# Receiver_V2.net
KiCad netlist of a schematic drawn in Altium Designer
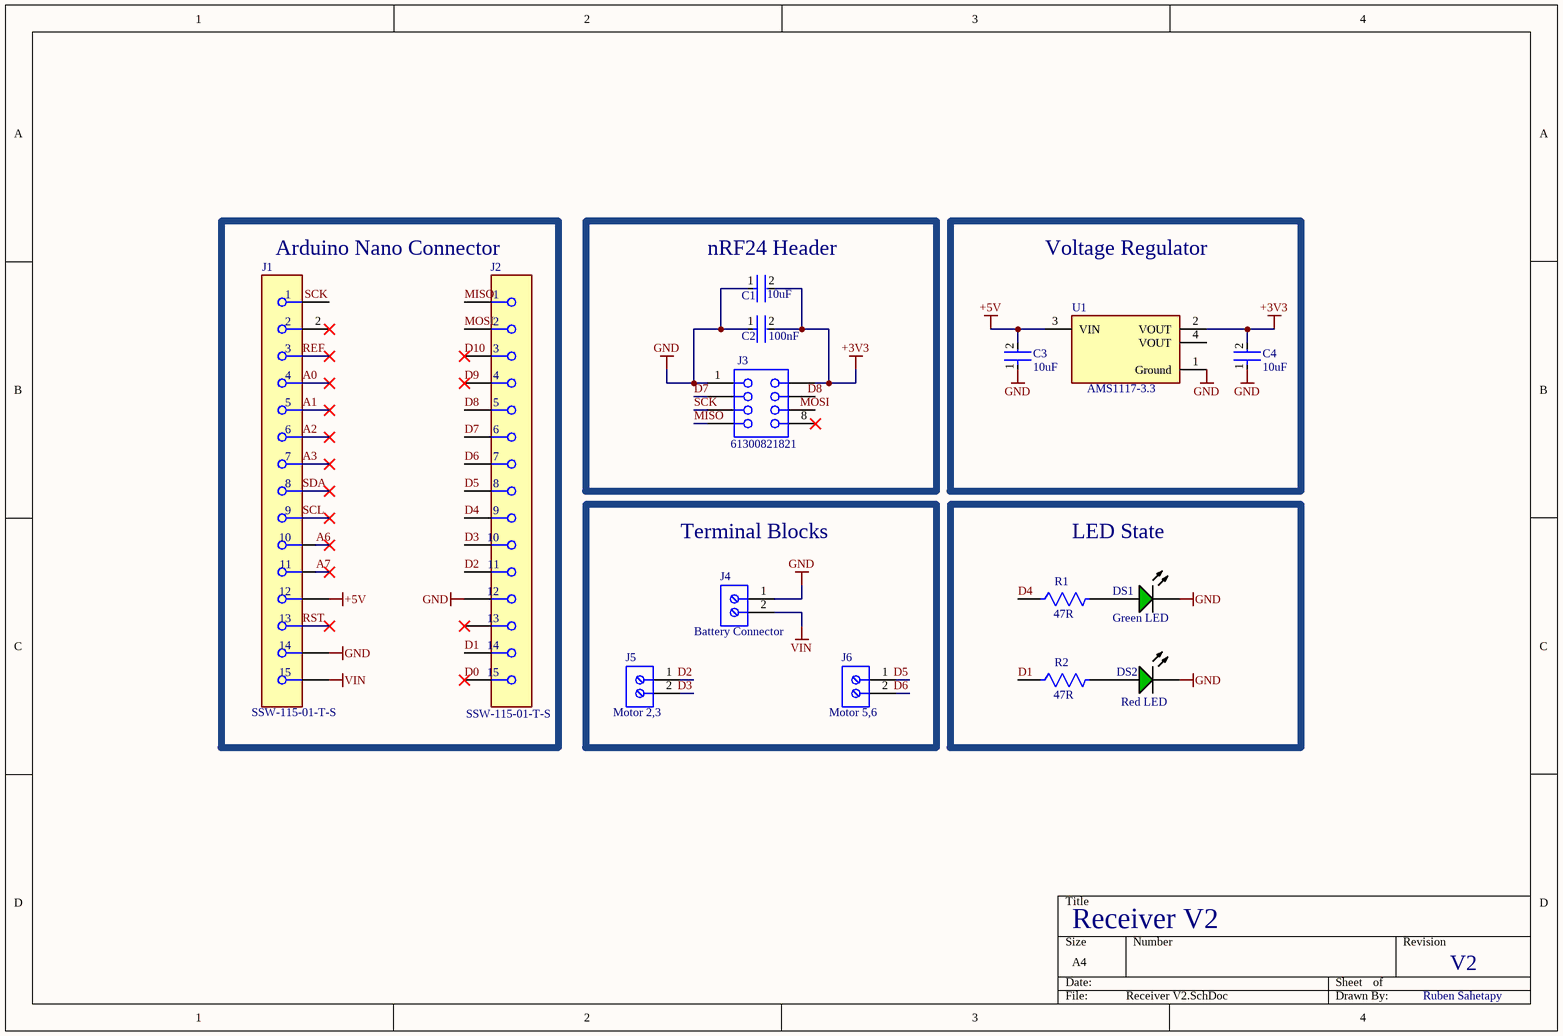
[diagram p0: Receiver V2.SchDoc]

(export (version "E")
  (design (tool "Eeschema 10.0.6"))
  (components
    (comp (ref "C1")
      (value "10uF")
      (footprint "FP-C0805C-DG-MFG")
      (description "CAP CER 10UF 10V X5R 0805")
      (fields (field (name "TOLERANCE") "10%") (field (name "MANUFACTURER PART NUMBER") "C0805C106K8PACTU"))
      (libsource (lib "Altium Content Vault") (part "11868f565c42a9108669ba33697ecf6"))
    )
    (comp (ref "C2")
      (value "100nF")
      (footprint "FP-CC0805-0_85-MFG")
      (description "CAP CER 0.1UF 16V X7R 0805")
      (fields
        (field (name "MANUFACTURER PART NUMBER") "CC0805KRX7R7BB104")
        (field (name "MANUFACTURER") "Yageo")
      )
      (libsource (lib "Altium Content Vault") (part "11868f565c42a9108669ba33697ecf6"))
    )
    (comp (ref "C3")
      (value "10uF")
      (footprint "FP-C0805C-DG-MFG")
      (description "CAP CER 10UF 10V X5R 0805")
      (fields (field (name "TOLERANCE") "10%") (field (name "MANUFACTURER PART NUMBER") "C0805C106K8PACTU"))
      (libsource (lib "Altium Content Vault") (part "11868f565c42a9108669ba33697ecf6"))
    )
    (comp (ref "C4")
      (value "10uF")
      (footprint "FP-C0805C-DG-MFG")
      (description "CAP CER 10UF 10V X5R 0805")
      (fields (field (name "TOLERANCE") "10%") (field (name "MANUFACTURER PART NUMBER") "C0805C106K8PACTU"))
      (libsource (lib "Altium Content Vault") (part "11868f565c42a9108669ba33697ecf6"))
    )
    (comp (ref "DS1")
      (value "Green LED")
      (footprint "AVAG-HSMX-C170_V")
      (description "Chip LED, Green, 2.2 V, -40 to 85 degC, 2-Pin SMD, Pb-Free, Tape and Reel")
      (fields (field (name "MANUFACTURER") "Avago"))
      (libsource (lib "Altium Content Vault") (part "LED_GREEN_A1K2-2"))
    )
    (comp (ref "DS2")
      (value "Red LED")
      (footprint "AVAG-HSMX-C170_V")
      (description "Chip LED, Green, 2.2 V, -40 to 85 degC, 2-Pin SMD, Pb-Free, Tape and Reel")
      (fields (field (name "MANUFACTURER") "Avago"))
      (libsource (lib "Altium Content Vault") (part "LED_GREEN_A1K2-2"))
    )
    (comp (ref "J1")
      (value "SSW-115-01-T-S")
      (footprint "FP-SSW-115-01-T-S-MFG")
      (description "CONN RCPT 15POS 0.1 TIN PCB")
      (libsource (lib "") (part "de2cdd76613f87adcba81301aaab7e9_1"))
    )
    (comp (ref "J2")
      (value "SSW-115-01-T-S")
      (footprint "FP-SSW-115-01-T-S-MFG")
      (description "CONN RCPT 15POS 0.1 TIN PCB")
      (libsource (lib "Altium Content Vault") (part "de2cdd76613f87adcba81301aaab7e9"))
    )
    (comp (ref "J3")
      (value "61300821821")
      (footprint "61300821821")
      (libsource (lib "Altium Content Vault") (part "Header_Female_2R_08P"))
    )
    (comp (ref "J4")
      (value "Battery Connector")
      (footprint "691214110002")
      (fields (field (name "VOLTAGE") "300V"))
      (libsource (lib "Altium Content Vault") (part "TBL - 1R - 02P - Screw"))
    )
    (comp (ref "J5")
      (value "Motor 2,3")
      (footprint "691214110002")
      (fields (field (name "VOLTAGE") "300V"))
      (libsource (lib "Altium Content Vault") (part "TBL - 1R - 02P - Screw"))
    )
    (comp (ref "J6")
      (value "Motor 5,6")
      (footprint "691214110002")
      (fields (field (name "VOLTAGE") "300V"))
      (libsource (lib "Altium Content Vault") (part "TBL - 1R - 02P - Screw"))
    )
    (comp (ref "R1")
      (value "47R")
      (footprint "FP-RC1206-MFG")
      (description "RES SMD 0 OHM JUMPER 1/4W 1206")
      (fields
        (field (name "MANUFACTURER PART NUMBER") "RC1206JR-070RL")
        (field (name "MANUFACTURER") "YAGEO")
      )
      (libsource (lib "Altium Content Vault") (part "1029c3af85768c4190bb7ad29bc67b5"))
    )
    (comp (ref "R2")
      (value "47R")
      (footprint "FP-RC1206-MFG")
      (description "RES SMD 0 OHM JUMPER 1/4W 1206")
      (fields
        (field (name "MANUFACTURER PART NUMBER") "RC1206JR-070RL")
        (field (name "MANUFACTURER") "YAGEO")
      )
      (libsource (lib "Altium Content Vault") (part "1029c3af85768c4190bb7ad29bc67b5"))
    )
    (comp (ref "U1")
      (value "AMS1117-3.3")
      (footprint "FP-AMS1117-IPC_C")
      (description "LDO Voltage Regulators 1A, 3.3V")
      (fields
        (field (name "OCTOPART") "https://octopart.com/ams1117-3.3-advanced+monolithic+systems-25899300")
        (field (name "MANUFACTURER") "Advanced Monolithic Systems")
      )
      (libsource (lib "Altium Content Vault") (part "8bdbb5f8e77002000e30dd2845d0354"))
    )
  )
  (nets
    (net (code "1") (name "+3V3") (class "Default")
      (node (ref "C1") (pin "2") (pinfunction "2_2") (pintype "passive"))
      (node (ref "C2") (pin "2") (pinfunction "2_2") (pintype "passive"))
      (node (ref "C4") (pin "2") (pinfunction "2_2") (pintype "passive"))
      (node (ref "J3") (pin "2") (pinfunction "2_2") (pintype "passive"))
      (node (ref "U1") (pin "2") (pinfunction "VOUT_2") (pintype "passive"))
    )
    (net (code "2") (name "+5V") (class "Default")
      (node (ref "C3") (pin "2") (pinfunction "2_2") (pintype "passive"))
      (node (ref "J1") (pin "12") (pinfunction "12_12") (pintype "passive"))
      (node (ref "U1") (pin "3") (pinfunction "VIN_3") (pintype "power_in"))
    )
    (net (code "3") (name "/A0") (class "Default")
      (node (ref "J1") (pin "4") (pinfunction "4_4") (pintype "passive+no_connect"))
    )
    (net (code "4") (name "/A1") (class "Default")
      (node (ref "J1") (pin "5") (pinfunction "5_5") (pintype "passive+no_connect"))
    )
    (net (code "5") (name "/A2") (class "Default")
      (node (ref "J1") (pin "6") (pinfunction "6_6") (pintype "passive+no_connect"))
    )
    (net (code "6") (name "/A3") (class "Default")
      (node (ref "J1") (pin "7") (pinfunction "7_7") (pintype "passive+no_connect"))
    )
    (net (code "7") (name "/A6") (class "Default")
      (node (ref "J1") (pin "10") (pinfunction "10_10") (pintype "passive+no_connect"))
    )
    (net (code "8") (name "/A7") (class "Default")
      (node (ref "J1") (pin "11") (pinfunction "11_11") (pintype "passive+no_connect"))
    )
    (net (code "9") (name "/D0") (class "Default")
      (node (ref "J2") (pin "15") (pinfunction "15_15") (pintype "passive+no_connect"))
    )
    (net (code "10") (name "/D1") (class "Default")
      (node (ref "J2") (pin "14") (pinfunction "14_14") (pintype "passive"))
      (node (ref "R2") (pin "1") (pinfunction "1_1") (pintype "passive"))
    )
    (net (code "11") (name "/D2") (class "Default")
      (node (ref "J2") (pin "11") (pinfunction "11_11") (pintype "passive"))
      (node (ref "J5") (pin "1") (pinfunction "1_1") (pintype "passive"))
    )
    (net (code "12") (name "/D3") (class "Default")
      (node (ref "J2") (pin "10") (pinfunction "10_10") (pintype "passive"))
      (node (ref "J5") (pin "2") (pinfunction "2_2") (pintype "passive"))
    )
    (net (code "13") (name "/D4") (class "Default")
      (node (ref "J2") (pin "9") (pinfunction "9_9") (pintype "passive"))
      (node (ref "R1") (pin "1") (pinfunction "1_1") (pintype "passive"))
    )
    (net (code "14") (name "/D5") (class "Default")
      (node (ref "J2") (pin "8") (pinfunction "8_8") (pintype "passive"))
      (node (ref "J6") (pin "1") (pinfunction "1_1") (pintype "passive"))
    )
    (net (code "15") (name "/D6") (class "Default")
      (node (ref "J2") (pin "7") (pinfunction "7_7") (pintype "passive"))
      (node (ref "J6") (pin "2") (pinfunction "2_2") (pintype "passive"))
    )
    (net (code "16") (name "/D7") (class "Default")
      (node (ref "J2") (pin "6") (pinfunction "6_6") (pintype "passive"))
      (node (ref "J3") (pin "3") (pinfunction "3_3") (pintype "passive"))
    )
    (net (code "17") (name "/D8") (class "Default")
      (node (ref "J2") (pin "5") (pinfunction "5_5") (pintype "passive"))
      (node (ref "J3") (pin "4") (pinfunction "4_4") (pintype "passive"))
    )
    (net (code "18") (name "/D9") (class "Default")
      (node (ref "J2") (pin "4") (pinfunction "4_4") (pintype "passive+no_connect"))
    )
    (net (code "19") (name "/D10") (class "Default")
      (node (ref "J2") (pin "3") (pinfunction "3_3") (pintype "passive+no_connect"))
    )
    (net (code "20") (name "/MISO") (class "Default")
      (node (ref "J2") (pin "1") (pinfunction "1_1") (pintype "passive"))
      (node (ref "J3") (pin "7") (pinfunction "7_7") (pintype "passive"))
    )
    (net (code "21") (name "/MOSI") (class "Default")
      (node (ref "J2") (pin "2") (pinfunction "2_2") (pintype "passive"))
      (node (ref "J3") (pin "6") (pinfunction "6_6") (pintype "passive"))
    )
    (net (code "22") (name "/REF") (class "Default")
      (node (ref "J1") (pin "3") (pinfunction "3_3") (pintype "passive+no_connect"))
    )
    (net (code "23") (name "/RST") (class "Default")
      (node (ref "J1") (pin "13") (pinfunction "13_13") (pintype "passive+no_connect"))
    )
    (net (code "24") (name "/SCK") (class "Default")
      (node (ref "J1") (pin "1") (pinfunction "1_1") (pintype "passive"))
      (node (ref "J3") (pin "5") (pinfunction "5_5") (pintype "passive"))
    )
    (net (code "25") (name "/SCL") (class "Default")
      (node (ref "J1") (pin "9") (pinfunction "9_9") (pintype "passive+no_connect"))
    )
    (net (code "26") (name "/SDA") (class "Default")
      (node (ref "J1") (pin "8") (pinfunction "8_8") (pintype "passive+no_connect"))
    )
    (net (code "27") (name "GND") (class "Default")
      (node (ref "C1") (pin "1") (pinfunction "1_1") (pintype "passive"))
      (node (ref "C2") (pin "1") (pinfunction "1_1") (pintype "passive"))
      (node (ref "C3") (pin "1") (pinfunction "1_1") (pintype "passive"))
      (node (ref "C4") (pin "1") (pinfunction "1_1") (pintype "passive"))
      (node (ref "DS1") (pin "2") (pinfunction "K_2") (pintype "passive"))
      (node (ref "DS2") (pin "2") (pinfunction "K_2") (pintype "passive"))
      (node (ref "J1") (pin "14") (pinfunction "14_14") (pintype "passive"))
      (node (ref "J2") (pin "12") (pinfunction "12_12") (pintype "passive"))
      (node (ref "J3") (pin "1") (pinfunction "1_1") (pintype "passive"))
      (node (ref "J4") (pin "1") (pinfunction "1_1") (pintype "passive"))
      (node (ref "U1") (pin "1") (pinfunction "Ground_1") (pintype "power_in"))
    )
    (net (code "28") (name "Net-(DS1-A)") (class "Default")
      (node (ref "DS1") (pin "1") (pinfunction "A_1") (pintype "passive"))
      (node (ref "R1") (pin "2") (pinfunction "2_2") (pintype "passive"))
    )
    (net (code "29") (name "Net-(DS2-A)") (class "Default")
      (node (ref "DS2") (pin "1") (pinfunction "A_1") (pintype "passive"))
      (node (ref "R2") (pin "2") (pinfunction "2_2") (pintype "passive"))
    )
    (net (code "30") (name "VIN") (class "Default")
      (node (ref "J1") (pin "15") (pinfunction "15_15") (pintype "passive"))
      (node (ref "J4") (pin "2") (pinfunction "2_2") (pintype "passive"))
    )
    (net (code "31") (name "unconnected-(J1-Pad2)") (class "Default")
      (node (ref "J1") (pin "2") (pinfunction "2_2") (pintype "passive+no_connect"))
    )
    (net (code "32") (name "unconnected-(J2-Pad13)") (class "Default")
      (node (ref "J2") (pin "13") (pinfunction "13_13") (pintype "passive+no_connect"))
    )
    (net (code "33") (name "unconnected-(J3-Pad8)") (class "Default")
      (node (ref "J3") (pin "8") (pinfunction "8_8") (pintype "passive+no_connect"))
    )
    (net (code "34") (name "unconnected-(U1-VOUT-Pad4)") (class "Default")
      (node (ref "U1") (pin "4") (pinfunction "VOUT_4") (pintype "passive"))
    )
  )
)
